# 08_MMC_SLOT.net
KiCad netlist of a schematic drawn in Altium Designer
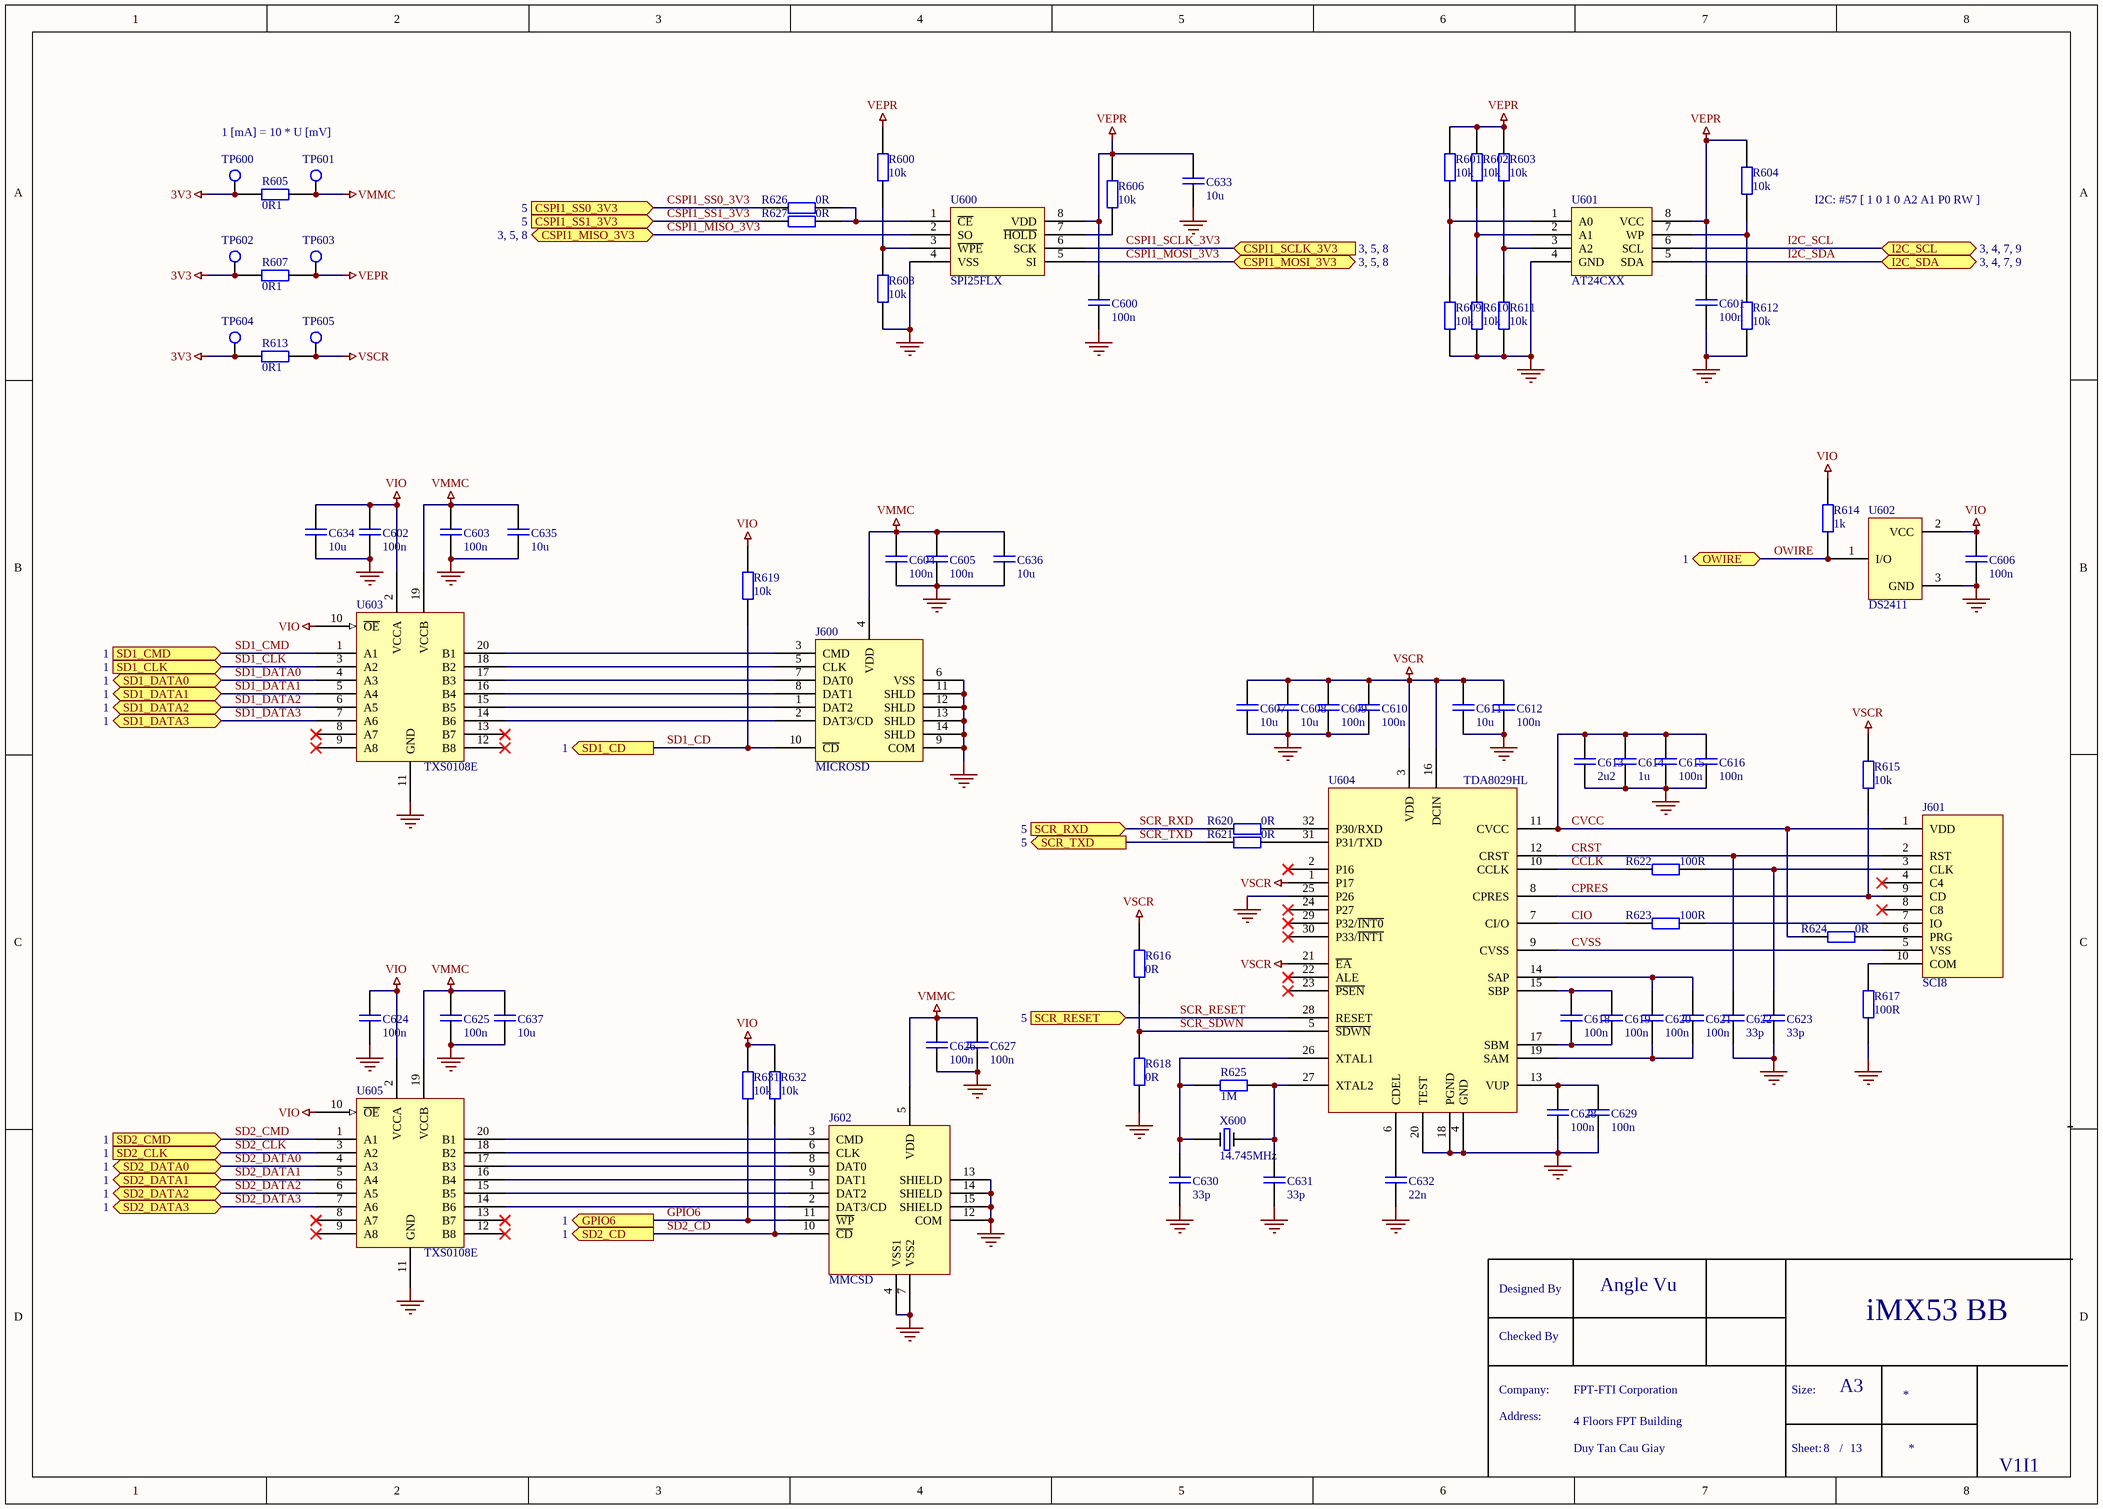
[diagram p0: [08] MMC SLOT.SchDoc]

(export (version "E")
  (design (tool "Eeschema 10.0.6"))
  (components
    (comp (ref "C600") (value "100n") (footprint "0603") (libsource (lib "imxbb") (part "C")))
    (comp (ref "C601") (value "100n") (footprint "0603") (libsource (lib "imxbb") (part "C")))
    (comp (ref "C602") (value "100n") (footprint "0603") (libsource (lib "imxbb") (part "C")))
    (comp (ref "C603") (value "100n") (footprint "0603") (libsource (lib "imxbb") (part "C")))
    (comp (ref "C604") (value "100n") (footprint "0603") (libsource (lib "imxbb") (part "C")))
    (comp (ref "C605") (value "100n") (footprint "0603") (libsource (lib "imxbb") (part "C")))
    (comp (ref "C606") (value "100n") (footprint "0603") (libsource (lib "imxbb") (part "C")))
    (comp (ref "C607") (value "10u") (footprint "0805") (libsource (lib "imxbb") (part "C")))
    (comp (ref "C608") (value "10u") (footprint "0805") (libsource (lib "imxbb") (part "C")))
    (comp (ref "C609") (value "100n") (footprint "0603") (libsource (lib "imxbb") (part "C")))
    (comp (ref "C610") (value "100n") (footprint "0603") (libsource (lib "imxbb") (part "C")))
    (comp (ref "C611") (value "10u") (footprint "0805") (libsource (lib "imxbb") (part "C")))
    (comp (ref "C612") (value "100n") (footprint "0603") (libsource (lib "imxbb") (part "C")))
    (comp (ref "C613") (value "2u2") (footprint "0603") (libsource (lib "imxbb") (part "C")))
    (comp (ref "C614") (value "1u") (footprint "0603") (libsource (lib "imxbb") (part "C")))
    (comp (ref "C615") (value "100n") (footprint "0603") (libsource (lib "imxbb") (part "C")))
    (comp (ref "C616") (value "100n") (footprint "0603") (libsource (lib "imxbb") (part "C")))
    (comp (ref "C618") (value "100n") (footprint "0603") (libsource (lib "imxbb") (part "C")))
    (comp (ref "C619") (value "100n") (footprint "0603") (libsource (lib "imxbb") (part "C")))
    (comp (ref "C620") (value "100n") (footprint "0603") (libsource (lib "imxbb") (part "C")))
    (comp (ref "C621") (value "100n") (footprint "0603") (libsource (lib "imxbb") (part "C")))
    (comp (ref "C622") (value "33p") (footprint "0603") (libsource (lib "imxbb") (part "C")))
    (comp (ref "C623") (value "33p") (footprint "0603") (libsource (lib "imxbb") (part "C")))
    (comp (ref "C624") (value "100n") (footprint "0603") (libsource (lib "imxbb") (part "C")))
    (comp (ref "C625") (value "100n") (footprint "0603") (libsource (lib "imxbb") (part "C")))
    (comp (ref "C626") (value "100n") (footprint "0603") (libsource (lib "imxbb") (part "C")))
    (comp (ref "C627") (value "100n") (footprint "0603") (libsource (lib "imxbb") (part "C")))
    (comp (ref "C628") (value "100n") (footprint "0603") (libsource (lib "imxbb") (part "C")))
    (comp (ref "C629") (value "100n") (footprint "0603") (libsource (lib "imxbb") (part "C")))
    (comp (ref "C630") (value "33p") (footprint "0603") (libsource (lib "imxbb") (part "C")))
    (comp (ref "C631") (value "33p") (footprint "0603") (libsource (lib "imxbb") (part "C")))
    (comp (ref "C632") (value "22n") (footprint "0603") (libsource (lib "imxbb") (part "C")))
    (comp (ref "C633") (value "10u") (footprint "0805") (libsource (lib "imxbb") (part "C")))
    (comp (ref "C634") (value "10u") (footprint "0805") (libsource (lib "imxbb") (part "C")))
    (comp (ref "C635") (value "10u") (footprint "0805") (libsource (lib "imxbb") (part "C")))
    (comp (ref "C636") (value "10u") (footprint "0805") (libsource (lib "imxbb") (part "C")))
    (comp (ref "C637") (value "10u") (footprint "0805") (libsource (lib "imxbb") (part "C")))
    (comp (ref "J600") (value "MICROSD") (footprint "uSD10") (libsource (lib "imxbb") (part "MICROSD")))
    (comp (ref "J601") (value "SCI8") (footprint "SCI8F") (libsource (lib "imxbb") (part "SCI8")))
    (comp (ref "J602") (value "MMCSD") (footprint "SDCMF-109") (libsource (lib "imxbb") (part "MMCSD")))
    (comp (ref "R600") (value "10k") (footprint "0603") (libsource (lib "") (part "R_1")))
    (comp (ref "R601") (value "10k") (footprint "0603") (libsource (lib "") (part "R_1")))
    (comp (ref "R602") (value "10k") (footprint "0603") (libsource (lib "") (part "R_1")))
    (comp (ref "R603") (value "10k") (footprint "0603") (libsource (lib "") (part "R_1")))
    (comp (ref "R604") (value "10k") (footprint "0603") (libsource (lib "") (part "R_1")))
    (comp (ref "R605") (value "0R1") (footprint "0603") (libsource (lib "") (part "R_4")))
    (comp (ref "R606") (value "10k") (footprint "0603") (libsource (lib "") (part "R_1")))
    (comp (ref "R607") (value "0R1") (footprint "0603") (libsource (lib "") (part "R_4")))
    (comp (ref "R608") (value "10k") (footprint "0603") (libsource (lib "") (part "R_1")))
    (comp (ref "R609") (value "10k") (footprint "0603") (libsource (lib "") (part "R_1")))
    (comp (ref "R610") (value "10k") (footprint "0603") (libsource (lib "") (part "R_1")))
    (comp (ref "R611") (value "10k") (footprint "0603") (libsource (lib "") (part "R_1")))
    (comp (ref "R612") (value "10k") (footprint "0603") (libsource (lib "") (part "R_1")))
    (comp (ref "R613") (value "0R1") (footprint "0603") (libsource (lib "") (part "R_4")))
    (comp (ref "R614") (value "1k") (footprint "0603") (libsource (lib "") (part "R_1")))
    (comp (ref "R615") (value "10k") (footprint "0603") (libsource (lib "imxbb") (part "R")))
    (comp (ref "R616") (value "0R") (footprint "0603") (libsource (lib "imxbb") (part "R")))
    (comp (ref "R617") (value "100R") (footprint "0603") (libsource (lib "imxbb") (part "R")))
    (comp (ref "R618") (value "0R") (footprint "0603") (libsource (lib "imxbb") (part "R")))
    (comp (ref "R619") (value "10k") (footprint "0603") (libsource (lib "") (part "R_1")))
    (comp (ref "R620") (value "0R") (footprint "0603") (libsource (lib "") (part "R_3")))
    (comp (ref "R621") (value "0R") (footprint "0603") (libsource (lib "") (part "R_3")))
    (comp (ref "R622") (value "100R") (footprint "0603") (libsource (lib "") (part "R_3")))
    (comp (ref "R623") (value "100R") (footprint "0603") (libsource (lib "") (part "R_3")))
    (comp (ref "R624") (value "0R") (footprint "0603") (libsource (lib "") (part "R_3")))
    (comp (ref "R625") (value "1M") (footprint "0603") (libsource (lib "") (part "R_2")))
    (comp (ref "R626") (value "0R") (footprint "0603") (libsource (lib "") (part "R_3")))
    (comp (ref "R627") (value "0R") (footprint "0603") (libsource (lib "") (part "R_3")))
    (comp (ref "R631") (value "10k") (footprint "0603") (libsource (lib "") (part "R_1")))
    (comp (ref "R632") (value "10k") (footprint "0603") (libsource (lib "") (part "R_1")))
    (comp (ref "TP600")
      (value "TESTPOINT")
      (footprint "TESTPOINT_2mm")
      (description "Testpoint pad")
      (libsource (lib "imxbb") (part "TESTPOINT"))
    )
    (comp (ref "TP601")
      (value "TESTPOINT")
      (footprint "TESTPOINT_2mm")
      (description "Testpoint pad")
      (libsource (lib "imxbb") (part "TESTPOINT"))
    )
    (comp (ref "TP602")
      (value "TESTPOINT")
      (footprint "TESTPOINT_2mm")
      (description "Testpoint pad")
      (libsource (lib "imxbb") (part "TESTPOINT"))
    )
    (comp (ref "TP603")
      (value "TESTPOINT")
      (footprint "TESTPOINT_2mm")
      (description "Testpoint pad")
      (libsource (lib "imxbb") (part "TESTPOINT"))
    )
    (comp (ref "TP604")
      (value "TESTPOINT")
      (footprint "TESTPOINT_2mm")
      (description "Testpoint pad")
      (libsource (lib "imxbb") (part "TESTPOINT"))
    )
    (comp (ref "TP605")
      (value "TESTPOINT")
      (footprint "TESTPOINT_2mm")
      (description "Testpoint pad")
      (libsource (lib "imxbb") (part "TESTPOINT"))
    )
    (comp (ref "U600") (value "SPI25FLX") (footprint "SOIC8") (libsource (lib "imxbb") (part "SPI25FLX")))
    (comp (ref "U601") (value "AT24CXX") (footprint "SOIC8") (libsource (lib "imxbb") (part "AT24CXX")))
    (comp (ref "U602") (value "DS2411") (footprint "SOT23") (libsource (lib "imxbb") (part "DS2411")))
    (comp (ref "U603") (value "TXS0108E") (footprint "TSSOP20") (libsource (lib "imxbb") (part "TXS0108E")))
    (comp (ref "U604") (value "TDA8029HL") (footprint "LQFP32") (libsource (lib "imxbb") (part "TDA8029HL")))
    (comp (ref "U605") (value "TXS0108E") (footprint "TSSOP20") (libsource (lib "imxbb") (part "TXS0108E")))
    (comp (ref "X600") (value "14.745MHz") (footprint "HC494H") (libsource (lib "imxbb") (part "XTAL")))
  )
  (nets
    (net (code "1") (name "/CCLK") (class "Default")
      (node (ref "R622") (pin "1") (pinfunction "1_1") (pintype "passive"))
      (node (ref "U604") (pin "10") (pinfunction "CCLK_10") (pintype "passive"))
    )
    (net (code "2") (name "/CIO") (class "Default")
      (node (ref "R623") (pin "1") (pinfunction "1_1") (pintype "passive"))
      (node (ref "U604") (pin "7") (pinfunction "CI/O_7") (pintype "passive"))
    )
    (net (code "3") (name "/CPRES") (class "Default")
      (node (ref "J601") (pin "9") (pinfunction "CD_9") (pintype "passive"))
      (node (ref "R615") (pin "1") (pinfunction "1_1") (pintype "passive"))
      (node (ref "U604") (pin "8") (pinfunction "CPRES_8") (pintype "passive"))
    )
    (net (code "4") (name "/CRST") (class "Default")
      (node (ref "C622") (pin "2") (pinfunction "2_2") (pintype "passive"))
      (node (ref "J601") (pin "2") (pinfunction "RST_2") (pintype "passive"))
      (node (ref "U604") (pin "12") (pinfunction "CRST_12") (pintype "passive"))
    )
    (net (code "5") (name "/CSPI1_MISO_3V3") (class "Default")
      (node (ref "U600") (pin "2") (pinfunction "SO_2") (pintype "passive"))
    )
    (net (code "6") (name "/CSPI1_MOSI_3V3") (class "Default")
      (node (ref "U600") (pin "5") (pinfunction "SI_5") (pintype "passive"))
    )
    (net (code "7") (name "/CSPI1_SCLK_3V3") (class "Default")
      (node (ref "U600") (pin "6") (pinfunction "SCK_6") (pintype "passive"))
    )
    (net (code "8") (name "/CSPI1_SS0_3V3") (class "Default")
      (node (ref "R626") (pin "1") (pinfunction "1_1") (pintype "passive"))
    )
    (net (code "9") (name "/CSPI1_SS1_3V3") (class "Default")
      (node (ref "R627") (pin "1") (pinfunction "1_1") (pintype "passive"))
    )
    (net (code "10") (name "/CVCC") (class "Default")
      (node (ref "C613") (pin "2") (pinfunction "2_2") (pintype "passive"))
      (node (ref "C614") (pin "2") (pinfunction "2_2") (pintype "passive"))
      (node (ref "C615") (pin "2") (pinfunction "2_2") (pintype "passive"))
      (node (ref "C616") (pin "2") (pinfunction "2_2") (pintype "passive"))
      (node (ref "J601") (pin "1") (pinfunction "VDD_1") (pintype "passive"))
      (node (ref "R624") (pin "1") (pinfunction "1_1") (pintype "passive"))
      (node (ref "U604") (pin "11") (pinfunction "CVCC_11") (pintype "passive"))
    )
    (net (code "11") (name "/CVSS") (class "Default")
      (node (ref "J601") (pin "5") (pinfunction "VSS_5") (pintype "passive"))
      (node (ref "U604") (pin "9") (pinfunction "CVSS_9") (pintype "passive"))
    )
    (net (code "12") (name "/GPIO6") (class "Default")
      (node (ref "J602") (pin "11") (pinfunction "~{WP}_11") (pintype "passive"))
      (node (ref "R631") (pin "2") (pinfunction "2_2") (pintype "passive"))
    )
    (net (code "13") (name "/I2C_SCL") (class "Default")
      (node (ref "U601") (pin "6") (pinfunction "SCL_6") (pintype "passive"))
    )
    (net (code "14") (name "/I2C_SDA") (class "Default")
      (node (ref "U601") (pin "5") (pinfunction "SDA_5") (pintype "passive"))
    )
    (net (code "15") (name "/OWIRE") (class "Default")
      (node (ref "R614") (pin "2") (pinfunction "2_2") (pintype "passive"))
      (node (ref "U602") (pin "1") (pinfunction "I/O_1") (pintype "passive"))
    )
    (net (code "16") (name "/SCR_RESET") (class "Default")
      (node (ref "U604") (pin "28") (pinfunction "RESET_28") (pintype "passive"))
    )
    (net (code "17") (name "/SCR_RXD") (class "Default")
      (node (ref "R620") (pin "1") (pinfunction "1_1") (pintype "passive"))
    )
    (net (code "18") (name "/SCR_SDWN") (class "Default")
      (node (ref "R616") (pin "1") (pinfunction "1_1") (pintype "passive"))
      (node (ref "R618") (pin "2") (pinfunction "2_2") (pintype "passive"))
      (node (ref "U604") (pin "5") (pinfunction "~{SDWN}_5") (pintype "passive"))
    )
    (net (code "19") (name "/SCR_TXD") (class "Default")
      (node (ref "R621") (pin "1") (pinfunction "1_1") (pintype "passive"))
    )
    (net (code "20") (name "/SD1_CD") (class "Default")
      (node (ref "J600") (pin "10") (pinfunction "~{CD}_10") (pintype "passive"))
      (node (ref "R619") (pin "2") (pinfunction "2_2") (pintype "passive"))
    )
    (net (code "21") (name "/SD1_CLK") (class "Default")
      (node (ref "U603") (pin "3") (pinfunction "A2_3") (pintype "passive"))
    )
    (net (code "22") (name "/SD1_CMD") (class "Default")
      (node (ref "U603") (pin "1") (pinfunction "A1_1") (pintype "passive"))
    )
    (net (code "23") (name "/SD1_DATA0") (class "Default")
      (node (ref "U603") (pin "4") (pinfunction "A3_4") (pintype "passive"))
    )
    (net (code "24") (name "/SD1_DATA1") (class "Default")
      (node (ref "U603") (pin "5") (pinfunction "A4_5") (pintype "passive"))
    )
    (net (code "25") (name "/SD1_DATA2") (class "Default")
      (node (ref "U603") (pin "6") (pinfunction "A5_6") (pintype "passive"))
    )
    (net (code "26") (name "/SD1_DATA3") (class "Default")
      (node (ref "U603") (pin "7") (pinfunction "A6_7") (pintype "passive"))
    )
    (net (code "27") (name "/SD2_CD") (class "Default")
      (node (ref "J602") (pin "10") (pinfunction "~{CD}_10") (pintype "passive"))
      (node (ref "R632") (pin "2") (pinfunction "2_2") (pintype "passive"))
    )
    (net (code "28") (name "/SD2_CLK") (class "Default")
      (node (ref "U605") (pin "3") (pinfunction "A2_3") (pintype "passive"))
    )
    (net (code "29") (name "/SD2_CMD") (class "Default")
      (node (ref "U605") (pin "1") (pinfunction "A1_1") (pintype "passive"))
    )
    (net (code "30") (name "/SD2_DATA0") (class "Default")
      (node (ref "U605") (pin "4") (pinfunction "A3_4") (pintype "passive"))
    )
    (net (code "31") (name "/SD2_DATA1") (class "Default")
      (node (ref "U605") (pin "5") (pinfunction "A4_5") (pintype "passive"))
    )
    (net (code "32") (name "/SD2_DATA2") (class "Default")
      (node (ref "U605") (pin "6") (pinfunction "A5_6") (pintype "passive"))
    )
    (net (code "33") (name "/SD2_DATA3") (class "Default")
      (node (ref "U605") (pin "7") (pinfunction "A6_7") (pintype "passive"))
    )
    (net (code "34") (name "3V3") (class "Default")
      (node (ref "R605") (pin "1") (pinfunction "1_1") (pintype "passive"))
      (node (ref "R607") (pin "1") (pinfunction "1_1") (pintype "passive"))
      (node (ref "R613") (pin "1") (pinfunction "1_1") (pintype "passive"))
      (node (ref "TP600") (pin "1") (pinfunction "1_1") (pintype "passive"))
      (node (ref "TP602") (pin "1") (pinfunction "1_1") (pintype "passive"))
      (node (ref "TP604") (pin "1") (pinfunction "1_1") (pintype "passive"))
    )
    (net (code "35") (name "GND") (class "Default")
      (node (ref "C600") (pin "1") (pinfunction "1_1") (pintype "passive"))
      (node (ref "C601") (pin "1") (pinfunction "1_1") (pintype "passive"))
      (node (ref "C602") (pin "1") (pinfunction "1_1") (pintype "passive"))
      (node (ref "C603") (pin "1") (pinfunction "1_1") (pintype "passive"))
      (node (ref "C604") (pin "1") (pinfunction "1_1") (pintype "passive"))
      (node (ref "C605") (pin "1") (pinfunction "1_1") (pintype "passive"))
      (node (ref "C606") (pin "1") (pinfunction "1_1") (pintype "passive"))
      (node (ref "C607") (pin "1") (pinfunction "1_1") (pintype "passive"))
      (node (ref "C608") (pin "1") (pinfunction "1_1") (pintype "passive"))
      (node (ref "C609") (pin "1") (pinfunction "1_1") (pintype "passive"))
      (node (ref "C610") (pin "1") (pinfunction "1_1") (pintype "passive"))
      (node (ref "C611") (pin "1") (pinfunction "1_1") (pintype "passive"))
      (node (ref "C612") (pin "1") (pinfunction "1_1") (pintype "passive"))
      (node (ref "C613") (pin "1") (pinfunction "1_1") (pintype "passive"))
      (node (ref "C614") (pin "1") (pinfunction "1_1") (pintype "passive"))
      (node (ref "C615") (pin "1") (pinfunction "1_1") (pintype "passive"))
      (node (ref "C616") (pin "1") (pinfunction "1_1") (pintype "passive"))
      (node (ref "C622") (pin "1") (pinfunction "1_1") (pintype "passive"))
      (node (ref "C623") (pin "1") (pinfunction "1_1") (pintype "passive"))
      (node (ref "C624") (pin "1") (pinfunction "1_1") (pintype "passive"))
      (node (ref "C625") (pin "1") (pinfunction "1_1") (pintype "passive"))
      (node (ref "C626") (pin "1") (pinfunction "1_1") (pintype "passive"))
      (node (ref "C627") (pin "1") (pinfunction "1_1") (pintype "passive"))
      (node (ref "C628") (pin "1") (pinfunction "1_1") (pintype "passive"))
      (node (ref "C629") (pin "1") (pinfunction "1_1") (pintype "passive"))
      (node (ref "C630") (pin "1") (pinfunction "1_1") (pintype "passive"))
      (node (ref "C631") (pin "1") (pinfunction "1_1") (pintype "passive"))
      (node (ref "C632") (pin "1") (pinfunction "1_1") (pintype "passive"))
      (node (ref "C633") (pin "1") (pinfunction "1_1") (pintype "passive"))
      (node (ref "C634") (pin "1") (pinfunction "1_1") (pintype "passive"))
      (node (ref "C635") (pin "1") (pinfunction "1_1") (pintype "passive"))
      (node (ref "C636") (pin "1") (pinfunction "1_1") (pintype "passive"))
      (node (ref "C637") (pin "1") (pinfunction "1_1") (pintype "passive"))
      (node (ref "J600") (pin "11") (pinfunction "SHLD_11") (pintype "passive"))
      (node (ref "J600") (pin "12") (pinfunction "SHLD_12") (pintype "passive"))
      (node (ref "J600") (pin "13") (pinfunction "SHLD_13") (pintype "passive"))
      (node (ref "J600") (pin "14") (pinfunction "SHLD_14") (pintype "passive"))
      (node (ref "J600") (pin "6") (pinfunction "VSS_6") (pintype "passive"))
      (node (ref "J600") (pin "9") (pinfunction "COM_9") (pintype "passive"))
      (node (ref "J602") (pin "12") (pinfunction "COM_12") (pintype "passive"))
      (node (ref "J602") (pin "13") (pinfunction "SHIELD_13") (pintype "passive"))
      (node (ref "J602") (pin "14") (pinfunction "SHIELD_14") (pintype "passive"))
      (node (ref "J602") (pin "15") (pinfunction "SHIELD_15") (pintype "passive"))
      (node (ref "J602") (pin "4") (pinfunction "VSS1_4") (pintype "passive"))
      (node (ref "J602") (pin "7") (pinfunction "VSS2_7") (pintype "passive"))
      (node (ref "R608") (pin "2") (pinfunction "2_2") (pintype "passive"))
      (node (ref "R609") (pin "2") (pinfunction "2_2") (pintype "passive"))
      (node (ref "R610") (pin "2") (pinfunction "2_2") (pintype "passive"))
      (node (ref "R611") (pin "2") (pinfunction "2_2") (pintype "passive"))
      (node (ref "R612") (pin "2") (pinfunction "2_2") (pintype "passive"))
      (node (ref "R617") (pin "1") (pinfunction "1_1") (pintype "passive"))
      (node (ref "R618") (pin "1") (pinfunction "1_1") (pintype "passive"))
      (node (ref "U600") (pin "4") (pinfunction "VSS_4") (pintype "passive"))
      (node (ref "U601") (pin "4") (pinfunction "GND_4") (pintype "passive"))
      (node (ref "U602") (pin "3") (pinfunction "GND_3") (pintype "passive"))
      (node (ref "U603") (pin "11") (pinfunction "GND_11") (pintype "power_in"))
      (node (ref "U604") (pin "18") (pinfunction "PGND_18") (pintype "passive"))
      (node (ref "U604") (pin "20") (pinfunction "TEST_20") (pintype "passive"))
      (node (ref "U604") (pin "25") (pinfunction "P26_25") (pintype "passive"))
      (node (ref "U604") (pin "4") (pinfunction "GND_4") (pintype "passive"))
      (node (ref "U605") (pin "11") (pinfunction "GND_11") (pintype "power_in"))
    )
    (net (code "36") (name "Net-(J600-CLK)") (class "Default")
      (node (ref "J600") (pin "5") (pinfunction "CLK_5") (pintype "passive"))
      (node (ref "U603") (pin "18") (pinfunction "B2_18") (pintype "passive"))
    )
    (net (code "37") (name "Net-(J600-CMD)") (class "Default")
      (node (ref "J600") (pin "3") (pinfunction "CMD_3") (pintype "passive"))
      (node (ref "U603") (pin "20") (pinfunction "B1_20") (pintype "passive"))
    )
    (net (code "38") (name "Net-(J600-DAT0)") (class "Default")
      (node (ref "J600") (pin "7") (pinfunction "DAT0_7") (pintype "passive"))
      (node (ref "U603") (pin "17") (pinfunction "B3_17") (pintype "passive"))
    )
    (net (code "39") (name "Net-(J600-DAT1)") (class "Default")
      (node (ref "J600") (pin "8") (pinfunction "DAT1_8") (pintype "passive"))
      (node (ref "U603") (pin "16") (pinfunction "B4_16") (pintype "passive"))
    )
    (net (code "40") (name "Net-(J600-DAT2)") (class "Default")
      (node (ref "J600") (pin "1") (pinfunction "DAT2_1") (pintype "passive"))
      (node (ref "U603") (pin "15") (pinfunction "B5_15") (pintype "passive"))
    )
    (net (code "41") (name "Net-(J600-DAT3{slash}CD)") (class "Default")
      (node (ref "J600") (pin "2") (pinfunction "DAT3/CD_2") (pintype "passive"))
      (node (ref "U603") (pin "14") (pinfunction "B6_14") (pintype "passive"))
    )
    (net (code "42") (name "Net-(J601-CLK)") (class "Default")
      (node (ref "C623") (pin "2") (pinfunction "2_2") (pintype "passive"))
      (node (ref "J601") (pin "3") (pinfunction "CLK_3") (pintype "passive"))
      (node (ref "R622") (pin "2") (pinfunction "2_2") (pintype "passive"))
    )
    (net (code "43") (name "Net-(J601-COM)") (class "Default")
      (node (ref "J601") (pin "10") (pinfunction "COM_10") (pintype "passive"))
      (node (ref "R617") (pin "2") (pinfunction "2_2") (pintype "passive"))
    )
    (net (code "44") (name "Net-(J601-IO)") (class "Default")
      (node (ref "J601") (pin "7") (pinfunction "IO_7") (pintype "passive"))
      (node (ref "R623") (pin "2") (pinfunction "2_2") (pintype "passive"))
    )
    (net (code "45") (name "Net-(J601-PRG)") (class "Default")
      (node (ref "J601") (pin "6") (pinfunction "PRG_6") (pintype "passive"))
      (node (ref "R624") (pin "2") (pinfunction "2_2") (pintype "passive"))
    )
    (net (code "46") (name "Net-(J602-CLK)") (class "Default")
      (node (ref "J602") (pin "6") (pinfunction "CLK_6") (pintype "passive"))
      (node (ref "U605") (pin "18") (pinfunction "B2_18") (pintype "passive"))
    )
    (net (code "47") (name "Net-(J602-CMD)") (class "Default")
      (node (ref "J602") (pin "3") (pinfunction "CMD_3") (pintype "passive"))
      (node (ref "U605") (pin "20") (pinfunction "B1_20") (pintype "passive"))
    )
    (net (code "48") (name "Net-(J602-DAT0)") (class "Default")
      (node (ref "J602") (pin "8") (pinfunction "DAT0_8") (pintype "passive"))
      (node (ref "U605") (pin "17") (pinfunction "B3_17") (pintype "passive"))
    )
    (net (code "49") (name "Net-(J602-DAT1)") (class "Default")
      (node (ref "J602") (pin "9") (pinfunction "DAT1_9") (pintype "passive"))
      (node (ref "U605") (pin "16") (pinfunction "B4_16") (pintype "passive"))
    )
    (net (code "50") (name "Net-(J602-DAT2)") (class "Default")
      (node (ref "J602") (pin "1") (pinfunction "DAT2_1") (pintype "passive"))
      (node (ref "U605") (pin "15") (pinfunction "B5_15") (pintype "passive"))
    )
    (net (code "51") (name "Net-(J602-DAT3{slash}CD)") (class "Default")
      (node (ref "J602") (pin "2") (pinfunction "DAT3/CD_2") (pintype "passive"))
      (node (ref "U605") (pin "14") (pinfunction "B6_14") (pintype "passive"))
    )
    (net (code "52") (name "Net-(U600-~{CE})") (class "Default")
      (node (ref "R626") (pin "2") (pinfunction "2_2") (pintype "passive"))
      (node (ref "R627") (pin "2") (pinfunction "2_2") (pintype "passive"))
      (node (ref "U600") (pin "1") (pinfunction "~{CE}_1") (pintype "passive"))
    )
    (net (code "53") (name "Net-(U600-~{HOLD})") (class "Default")
      (node (ref "R606") (pin "2") (pinfunction "2_2") (pintype "passive"))
      (node (ref "U600") (pin "7") (pinfunction "~{HOLD}_7") (pintype "passive"))
    )
    (net (code "54") (name "Net-(U600-~{WPE})") (class "Default")
      (node (ref "R600") (pin "2") (pinfunction "2_2") (pintype "passive"))
      (node (ref "R608") (pin "1") (pinfunction "1_1") (pintype "passive"))
      (node (ref "U600") (pin "3") (pinfunction "~{WPE}_3") (pintype "passive"))
    )
    (net (code "55") (name "Net-(U601-A0)") (class "Default")
      (node (ref "R601") (pin "2") (pinfunction "2_2") (pintype "passive"))
      (node (ref "R609") (pin "1") (pinfunction "1_1") (pintype "passive"))
      (node (ref "U601") (pin "1") (pinfunction "A0_1") (pintype "passive"))
    )
    (net (code "56") (name "Net-(U601-A1)") (class "Default")
      (node (ref "R602") (pin "2") (pinfunction "2_2") (pintype "passive"))
      (node (ref "R610") (pin "1") (pinfunction "1_1") (pintype "passive"))
      (node (ref "U601") (pin "2") (pinfunction "A1_2") (pintype "passive"))
    )
    (net (code "57") (name "Net-(U601-A2)") (class "Default")
      (node (ref "R603") (pin "2") (pinfunction "2_2") (pintype "passive"))
      (node (ref "R611") (pin "1") (pinfunction "1_1") (pintype "passive"))
      (node (ref "U601") (pin "3") (pinfunction "A2_3") (pintype "passive"))
    )
    (net (code "58") (name "Net-(U601-WP)") (class "Default")
      (node (ref "R604") (pin "2") (pinfunction "2_2") (pintype "passive"))
      (node (ref "R612") (pin "1") (pinfunction "1_1") (pintype "passive"))
      (node (ref "U601") (pin "7") (pinfunction "WP_7") (pintype "passive"))
    )
    (net (code "59") (name "Net-(U604-CDEL)") (class "Default")
      (node (ref "C632") (pin "2") (pinfunction "2_2") (pintype "passive"))
      (node (ref "U604") (pin "6") (pinfunction "CDEL_6") (pintype "passive"))
    )
    (net (code "60") (name "Net-(U604-P30{slash}RXD)") (class "Default")
      (node (ref "R620") (pin "2") (pinfunction "2_2") (pintype "passive"))
      (node (ref "U604") (pin "32") (pinfunction "P30/RXD_32") (pintype "passive"))
    )
    (net (code "61") (name "Net-(U604-P31{slash}TXD)") (class "Default")
      (node (ref "R621") (pin "2") (pinfunction "2_2") (pintype "passive"))
      (node (ref "U604") (pin "31") (pinfunction "P31/TXD_31") (pintype "passive"))
    )
    (net (code "62") (name "Net-(U604-SAM)") (class "Default")
      (node (ref "C620") (pin "1") (pinfunction "1_1") (pintype "passive"))
      (node (ref "C621") (pin "1") (pinfunction "1_1") (pintype "passive"))
      (node (ref "U604") (pin "19") (pinfunction "SAM_19") (pintype "passive"))
    )
    (net (code "63") (name "Net-(U604-SAP)") (class "Default")
      (node (ref "C620") (pin "2") (pinfunction "2_2") (pintype "passive"))
      (node (ref "C621") (pin "2") (pinfunction "2_2") (pintype "passive"))
      (node (ref "U604") (pin "14") (pinfunction "SAP_14") (pintype "passive"))
    )
    (net (code "64") (name "Net-(U604-SBM)") (class "Default")
      (node (ref "C618") (pin "1") (pinfunction "1_1") (pintype "passive"))
      (node (ref "C619") (pin "1") (pinfunction "1_1") (pintype "passive"))
      (node (ref "U604") (pin "17") (pinfunction "SBM_17") (pintype "passive"))
    )
    (net (code "65") (name "Net-(U604-SBP)") (class "Default")
      (node (ref "C618") (pin "2") (pinfunction "2_2") (pintype "passive"))
      (node (ref "C619") (pin "2") (pinfunction "2_2") (pintype "passive"))
      (node (ref "U604") (pin "15") (pinfunction "SBP_15") (pintype "passive"))
    )
    (net (code "66") (name "Net-(U604-VUP)") (class "Default")
      (node (ref "C628") (pin "2") (pinfunction "2_2") (pintype "passive"))
      (node (ref "C629") (pin "2") (pinfunction "2_2") (pintype "passive"))
      (node (ref "U604") (pin "13") (pinfunction "VUP_13") (pintype "passive"))
    )
    (net (code "67") (name "Net-(U604-XTAL1)") (class "Default")
      (node (ref "C630") (pin "2") (pinfunction "2_2") (pintype "passive"))
      (node (ref "R625") (pin "2") (pinfunction "2_2") (pintype "passive"))
      (node (ref "U604") (pin "26") (pinfunction "XTAL1_26") (pintype "passive"))
      (node (ref "X600") (pin "1") (pinfunction "1_1") (pintype "passive"))
    )
    (net (code "68") (name "Net-(U604-XTAL2)") (class "Default")
      (node (ref "C631") (pin "2") (pinfunction "2_2") (pintype "passive"))
      (node (ref "R625") (pin "1") (pinfunction "1_1") (pintype "passive"))
      (node (ref "U604") (pin "27") (pinfunction "XTAL2_27") (pintype "passive"))
      (node (ref "X600") (pin "2") (pinfunction "2_2") (pintype "passive"))
    )
    (net (code "69") (name "VEPR") (class "Default")
      (node (ref "C600") (pin "2") (pinfunction "2_2") (pintype "passive"))
      (node (ref "C601") (pin "2") (pinfunction "2_2") (pintype "passive"))
      (node (ref "C633") (pin "2") (pinfunction "2_2") (pintype "passive"))
      (node (ref "R600") (pin "1") (pinfunction "1_1") (pintype "passive"))
      (node (ref "R601") (pin "1") (pinfunction "1_1") (pintype "passive"))
      (node (ref "R602") (pin "1") (pinfunction "1_1") (pintype "passive"))
      (node (ref "R603") (pin "1") (pinfunction "1_1") (pintype "passive"))
      (node (ref "R604") (pin "1") (pinfunction "1_1") (pintype "passive"))
      (node (ref "R606") (pin "1") (pinfunction "1_1") (pintype "passive"))
      (node (ref "R607") (pin "2") (pinfunction "2_2") (pintype "passive"))
      (node (ref "TP603") (pin "1") (pinfunction "1_1") (pintype "passive"))
      (node (ref "U600") (pin "8") (pinfunction "VDD_8") (pintype "passive"))
      (node (ref "U601") (pin "8") (pinfunction "VCC_8") (pintype "passive"))
    )
    (net (code "70") (name "VIO") (class "Default")
      (node (ref "C602") (pin "2") (pinfunction "2_2") (pintype "passive"))
      (node (ref "C606") (pin "2") (pinfunction "2_2") (pintype "passive"))
      (node (ref "C624") (pin "2") (pinfunction "2_2") (pintype "passive"))
      (node (ref "C634") (pin "2") (pinfunction "2_2") (pintype "passive"))
      (node (ref "R614") (pin "1") (pinfunction "1_1") (pintype "passive"))
      (node (ref "R619") (pin "1") (pinfunction "1_1") (pintype "passive"))
      (node (ref "R631") (pin "1") (pinfunction "1_1") (pintype "passive"))
      (node (ref "R632") (pin "1") (pinfunction "1_1") (pintype "passive"))
      (node (ref "U602") (pin "2") (pinfunction "VCC_2") (pintype "passive"))
      (node (ref "U603") (pin "10") (pinfunction "~{OE}_10") (pintype "input"))
      (node (ref "U603") (pin "2") (pinfunction "VCCA_2") (pintype "power_in"))
      (node (ref "U605") (pin "10") (pinfunction "~{OE}_10") (pintype "input"))
      (node (ref "U605") (pin "2") (pinfunction "VCCA_2") (pintype "power_in"))
    )
    (net (code "71") (name "VMMC") (class "Default")
      (node (ref "C603") (pin "2") (pinfunction "2_2") (pintype "passive"))
      (node (ref "C604") (pin "2") (pinfunction "2_2") (pintype "passive"))
      (node (ref "C605") (pin "2") (pinfunction "2_2") (pintype "passive"))
      (node (ref "C625") (pin "2") (pinfunction "2_2") (pintype "passive"))
      (node (ref "C626") (pin "2") (pinfunction "2_2") (pintype "passive"))
      (node (ref "C627") (pin "2") (pinfunction "2_2") (pintype "passive"))
      (node (ref "C635") (pin "2") (pinfunction "2_2") (pintype "passive"))
      (node (ref "C636") (pin "2") (pinfunction "2_2") (pintype "passive"))
      (node (ref "C637") (pin "2") (pinfunction "2_2") (pintype "passive"))
      (node (ref "J600") (pin "4") (pinfunction "VDD_4") (pintype "passive"))
      (node (ref "J602") (pin "5") (pinfunction "VDD_5") (pintype "passive"))
      (node (ref "R605") (pin "2") (pinfunction "2_2") (pintype "passive"))
      (node (ref "TP601") (pin "1") (pinfunction "1_1") (pintype "passive"))
      (node (ref "U603") (pin "19") (pinfunction "VCCB_19") (pintype "power_in"))
      (node (ref "U605") (pin "19") (pinfunction "VCCB_19") (pintype "power_in"))
    )
    (net (code "72") (name "VSCR") (class "Default")
      (node (ref "C607") (pin "2") (pinfunction "2_2") (pintype "passive"))
      (node (ref "C608") (pin "2") (pinfunction "2_2") (pintype "passive"))
      (node (ref "C609") (pin "2") (pinfunction "2_2") (pintype "passive"))
      (node (ref "C610") (pin "2") (pinfunction "2_2") (pintype "passive"))
      (node (ref "C611") (pin "2") (pinfunction "2_2") (pintype "passive"))
      (node (ref "C612") (pin "2") (pinfunction "2_2") (pintype "passive"))
      (node (ref "R613") (pin "2") (pinfunction "2_2") (pintype "passive"))
      (node (ref "R615") (pin "2") (pinfunction "2_2") (pintype "passive"))
      (node (ref "R616") (pin "2") (pinfunction "2_2") (pintype "passive"))
      (node (ref "TP605") (pin "1") (pinfunction "1_1") (pintype "passive"))
      (node (ref "U604") (pin "1") (pinfunction "P17_1") (pintype "passive"))
      (node (ref "U604") (pin "16") (pinfunction "DCIN_16") (pintype "passive"))
      (node (ref "U604") (pin "21") (pinfunction "~{EA}_21") (pintype "passive"))
      (node (ref "U604") (pin "3") (pinfunction "VDD_3") (pintype "passive"))
    )
    (net (code "73") (name "unconnected-(J601-C4-Pad4)") (class "Default")
      (node (ref "J601") (pin "4") (pinfunction "C4_4") (pintype "passive+no_connect"))
    )
    (net (code "74") (name "unconnected-(J601-C8-Pad8)") (class "Default")
      (node (ref "J601") (pin "8") (pinfunction "C8_8") (pintype "passive+no_connect"))
    )
    (net (code "75") (name "unconnected-(U603-A7-Pad8)") (class "Default")
      (node (ref "U603") (pin "8") (pinfunction "A7_8") (pintype "passive+no_connect"))
    )
    (net (code "76") (name "unconnected-(U603-A8-Pad9)") (class "Default")
      (node (ref "U603") (pin "9") (pinfunction "A8_9") (pintype "passive+no_connect"))
    )
    (net (code "77") (name "unconnected-(U603-B7-Pad13)") (class "Default")
      (node (ref "U603") (pin "13") (pinfunction "B7_13") (pintype "passive+no_connect"))
    )
    (net (code "78") (name "unconnected-(U603-B8-Pad12)") (class "Default")
      (node (ref "U603") (pin "12") (pinfunction "B8_12") (pintype "passive+no_connect"))
    )
    (net (code "79") (name "unconnected-(U604-ALE-Pad22)") (class "Default")
      (node (ref "U604") (pin "22") (pinfunction "ALE_22") (pintype "passive+no_connect"))
    )
    (net (code "80") (name "unconnected-(U604-P16-Pad2)") (class "Default")
      (node (ref "U604") (pin "2") (pinfunction "P16_2") (pintype "passive+no_connect"))
    )
    (net (code "81") (name "unconnected-(U604-P27-Pad24)") (class "Default")
      (node (ref "U604") (pin "24") (pinfunction "P27_24") (pintype "passive+no_connect"))
    )
    (net (code "82") (name "unconnected-(U604-P32{slash}~{INT0}-Pad29)") (class "Default")
      (node (ref "U604") (pin "29") (pinfunction "P32/~{INT0}_29") (pintype "passive+no_connect"))
    )
    (net (code "83") (name "unconnected-(U604-P33{slash}~{INT1}-Pad30)") (class "Default")
      (node (ref "U604") (pin "30") (pinfunction "P33/~{INT1}_30") (pintype "passive+no_connect"))
    )
    (net (code "84") (name "unconnected-(U604-~{PSEN}-Pad23)") (class "Default")
      (node (ref "U604") (pin "23") (pinfunction "~{PSEN}_23") (pintype "passive+no_connect"))
    )
    (net (code "85") (name "unconnected-(U605-A7-Pad8)") (class "Default")
      (node (ref "U605") (pin "8") (pinfunction "A7_8") (pintype "passive+no_connect"))
    )
    (net (code "86") (name "unconnected-(U605-A8-Pad9)") (class "Default")
      (node (ref "U605") (pin "9") (pinfunction "A8_9") (pintype "passive+no_connect"))
    )
    (net (code "87") (name "unconnected-(U605-B7-Pad13)") (class "Default")
      (node (ref "U605") (pin "13") (pinfunction "B7_13") (pintype "passive+no_connect"))
    )
    (net (code "88") (name "unconnected-(U605-B8-Pad12)") (class "Default")
      (node (ref "U605") (pin "12") (pinfunction "B8_12") (pintype "passive+no_connect"))
    )
  )
)
